# Sch_Sensores.net
KiCad netlist of a schematic drawn in Altium Designer
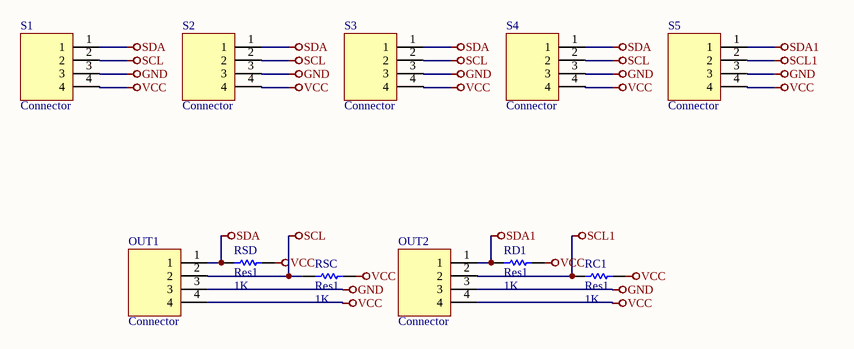
[diagram p0: Sch_Sensores.SchDoc]

(export (version "E")
  (design (tool "Eeschema 10.0.6"))
  (components
    (comp (ref "OUT1")
      (value "Connector")
      (footprint "1x4x2.54 Pin Header TH V")
      (libsource (lib "CARO") (part "Header 1x4"))
    )
    (comp (ref "OUT2")
      (value "Connector")
      (footprint "1x4x2.54 Pin Header TH V")
      (libsource (lib "CARO") (part "Header 1x4"))
    )
    (comp (ref "RC1")
      (value "Res1")
      (footprint "AXIAL-0.3")
      (description "Resistor")
      (fields (field (name "ALTIUM_VALUE") "1K") (field (name "PUBLISHER") "Altium Limited"))
      (libsource (lib "Miscellaneous Devices") (part "Res1"))
    )
    (comp (ref "RD1")
      (value "Res1")
      (footprint "AXIAL-0.3")
      (description "Resistor")
      (fields (field (name "ALTIUM_VALUE") "1K") (field (name "PUBLISHER") "Altium Limited"))
      (libsource (lib "Miscellaneous Devices") (part "Res1"))
    )
    (comp (ref "RSC")
      (value "Res1")
      (footprint "AXIAL-0.3")
      (description "Resistor")
      (fields (field (name "ALTIUM_VALUE") "1K") (field (name "PUBLISHER") "Altium Limited"))
      (libsource (lib "Miscellaneous Devices") (part "Res1"))
    )
    (comp (ref "RSD")
      (value "Res1")
      (footprint "AXIAL-0.3")
      (description "Resistor")
      (fields (field (name "ALTIUM_VALUE") "1K") (field (name "PUBLISHER") "Altium Limited"))
      (libsource (lib "Miscellaneous Devices") (part "Res1"))
    )
    (comp (ref "S1")
      (value "Connector")
      (footprint "1x4x2.54 Pin Header TH V")
      (libsource (lib "CARO") (part "Header 1x4"))
    )
    (comp (ref "S2")
      (value "Connector")
      (footprint "1x4x2.54 Pin Header TH V")
      (libsource (lib "CARO") (part "Header 1x4"))
    )
    (comp (ref "S3")
      (value "Connector")
      (footprint "1x4x2.54 Pin Header TH V")
      (libsource (lib "CARO") (part "Header 1x4"))
    )
    (comp (ref "S4")
      (value "Connector")
      (footprint "1x4x2.54 Pin Header TH V")
      (libsource (lib "CARO") (part "Header 1x4"))
    )
    (comp (ref "S5")
      (value "Connector")
      (footprint "1x4x2.54 Pin Header TH V")
      (libsource (lib "CARO") (part "Header 1x4"))
    )
  )
  (nets
    (net (code "1") (name "GND") (class "Default")
      (node (ref "OUT1") (pin "3") (pinfunction "3_3") (pintype "passive"))
      (node (ref "OUT2") (pin "3") (pinfunction "3_3") (pintype "passive"))
      (node (ref "S1") (pin "3") (pinfunction "3_3") (pintype "passive"))
      (node (ref "S2") (pin "3") (pinfunction "3_3") (pintype "passive"))
      (node (ref "S3") (pin "3") (pinfunction "3_3") (pintype "passive"))
      (node (ref "S4") (pin "3") (pinfunction "3_3") (pintype "passive"))
      (node (ref "S5") (pin "3") (pinfunction "3_3") (pintype "passive"))
    )
    (net (code "2") (name "SCL") (class "Default")
      (node (ref "OUT1") (pin "2") (pinfunction "2_2") (pintype "passive"))
      (node (ref "RSC") (pin "1") (pinfunction "1_1") (pintype "passive"))
      (node (ref "S1") (pin "2") (pinfunction "2_2") (pintype "passive"))
      (node (ref "S2") (pin "2") (pinfunction "2_2") (pintype "passive"))
      (node (ref "S3") (pin "2") (pinfunction "2_2") (pintype "passive"))
      (node (ref "S4") (pin "2") (pinfunction "2_2") (pintype "passive"))
    )
    (net (code "3") (name "SCL1") (class "Default")
      (node (ref "OUT2") (pin "2") (pinfunction "2_2") (pintype "passive"))
      (node (ref "RC1") (pin "1") (pinfunction "1_1") (pintype "passive"))
      (node (ref "S5") (pin "2") (pinfunction "2_2") (pintype "passive"))
    )
    (net (code "4") (name "SDA") (class "Default")
      (node (ref "OUT1") (pin "1") (pinfunction "1_1") (pintype "passive"))
      (node (ref "RSD") (pin "1") (pinfunction "1_1") (pintype "passive"))
      (node (ref "S1") (pin "1") (pinfunction "1_1") (pintype "passive"))
      (node (ref "S2") (pin "1") (pinfunction "1_1") (pintype "passive"))
      (node (ref "S3") (pin "1") (pinfunction "1_1") (pintype "passive"))
      (node (ref "S4") (pin "1") (pinfunction "1_1") (pintype "passive"))
    )
    (net (code "5") (name "SDA1") (class "Default")
      (node (ref "OUT2") (pin "1") (pinfunction "1_1") (pintype "passive"))
      (node (ref "RD1") (pin "1") (pinfunction "1_1") (pintype "passive"))
      (node (ref "S5") (pin "1") (pinfunction "1_1") (pintype "passive"))
    )
    (net (code "6") (name "VCC") (class "Default")
      (node (ref "OUT1") (pin "4") (pinfunction "4_4") (pintype "passive"))
      (node (ref "OUT2") (pin "4") (pinfunction "4_4") (pintype "passive"))
      (node (ref "RC1") (pin "2") (pinfunction "2_2") (pintype "passive"))
      (node (ref "RD1") (pin "2") (pinfunction "2_2") (pintype "passive"))
      (node (ref "RSC") (pin "2") (pinfunction "2_2") (pintype "passive"))
      (node (ref "RSD") (pin "2") (pinfunction "2_2") (pintype "passive"))
      (node (ref "S1") (pin "4") (pinfunction "4_4") (pintype "passive"))
      (node (ref "S2") (pin "4") (pinfunction "4_4") (pintype "passive"))
      (node (ref "S3") (pin "4") (pinfunction "4_4") (pintype "passive"))
      (node (ref "S4") (pin "4") (pinfunction "4_4") (pintype "passive"))
      (node (ref "S5") (pin "4") (pinfunction "4_4") (pintype "passive"))
    )
  )
)
